# P-MT3620RDB-1-7_PMU.net
KiCad netlist of a schematic drawn in Altium Designer
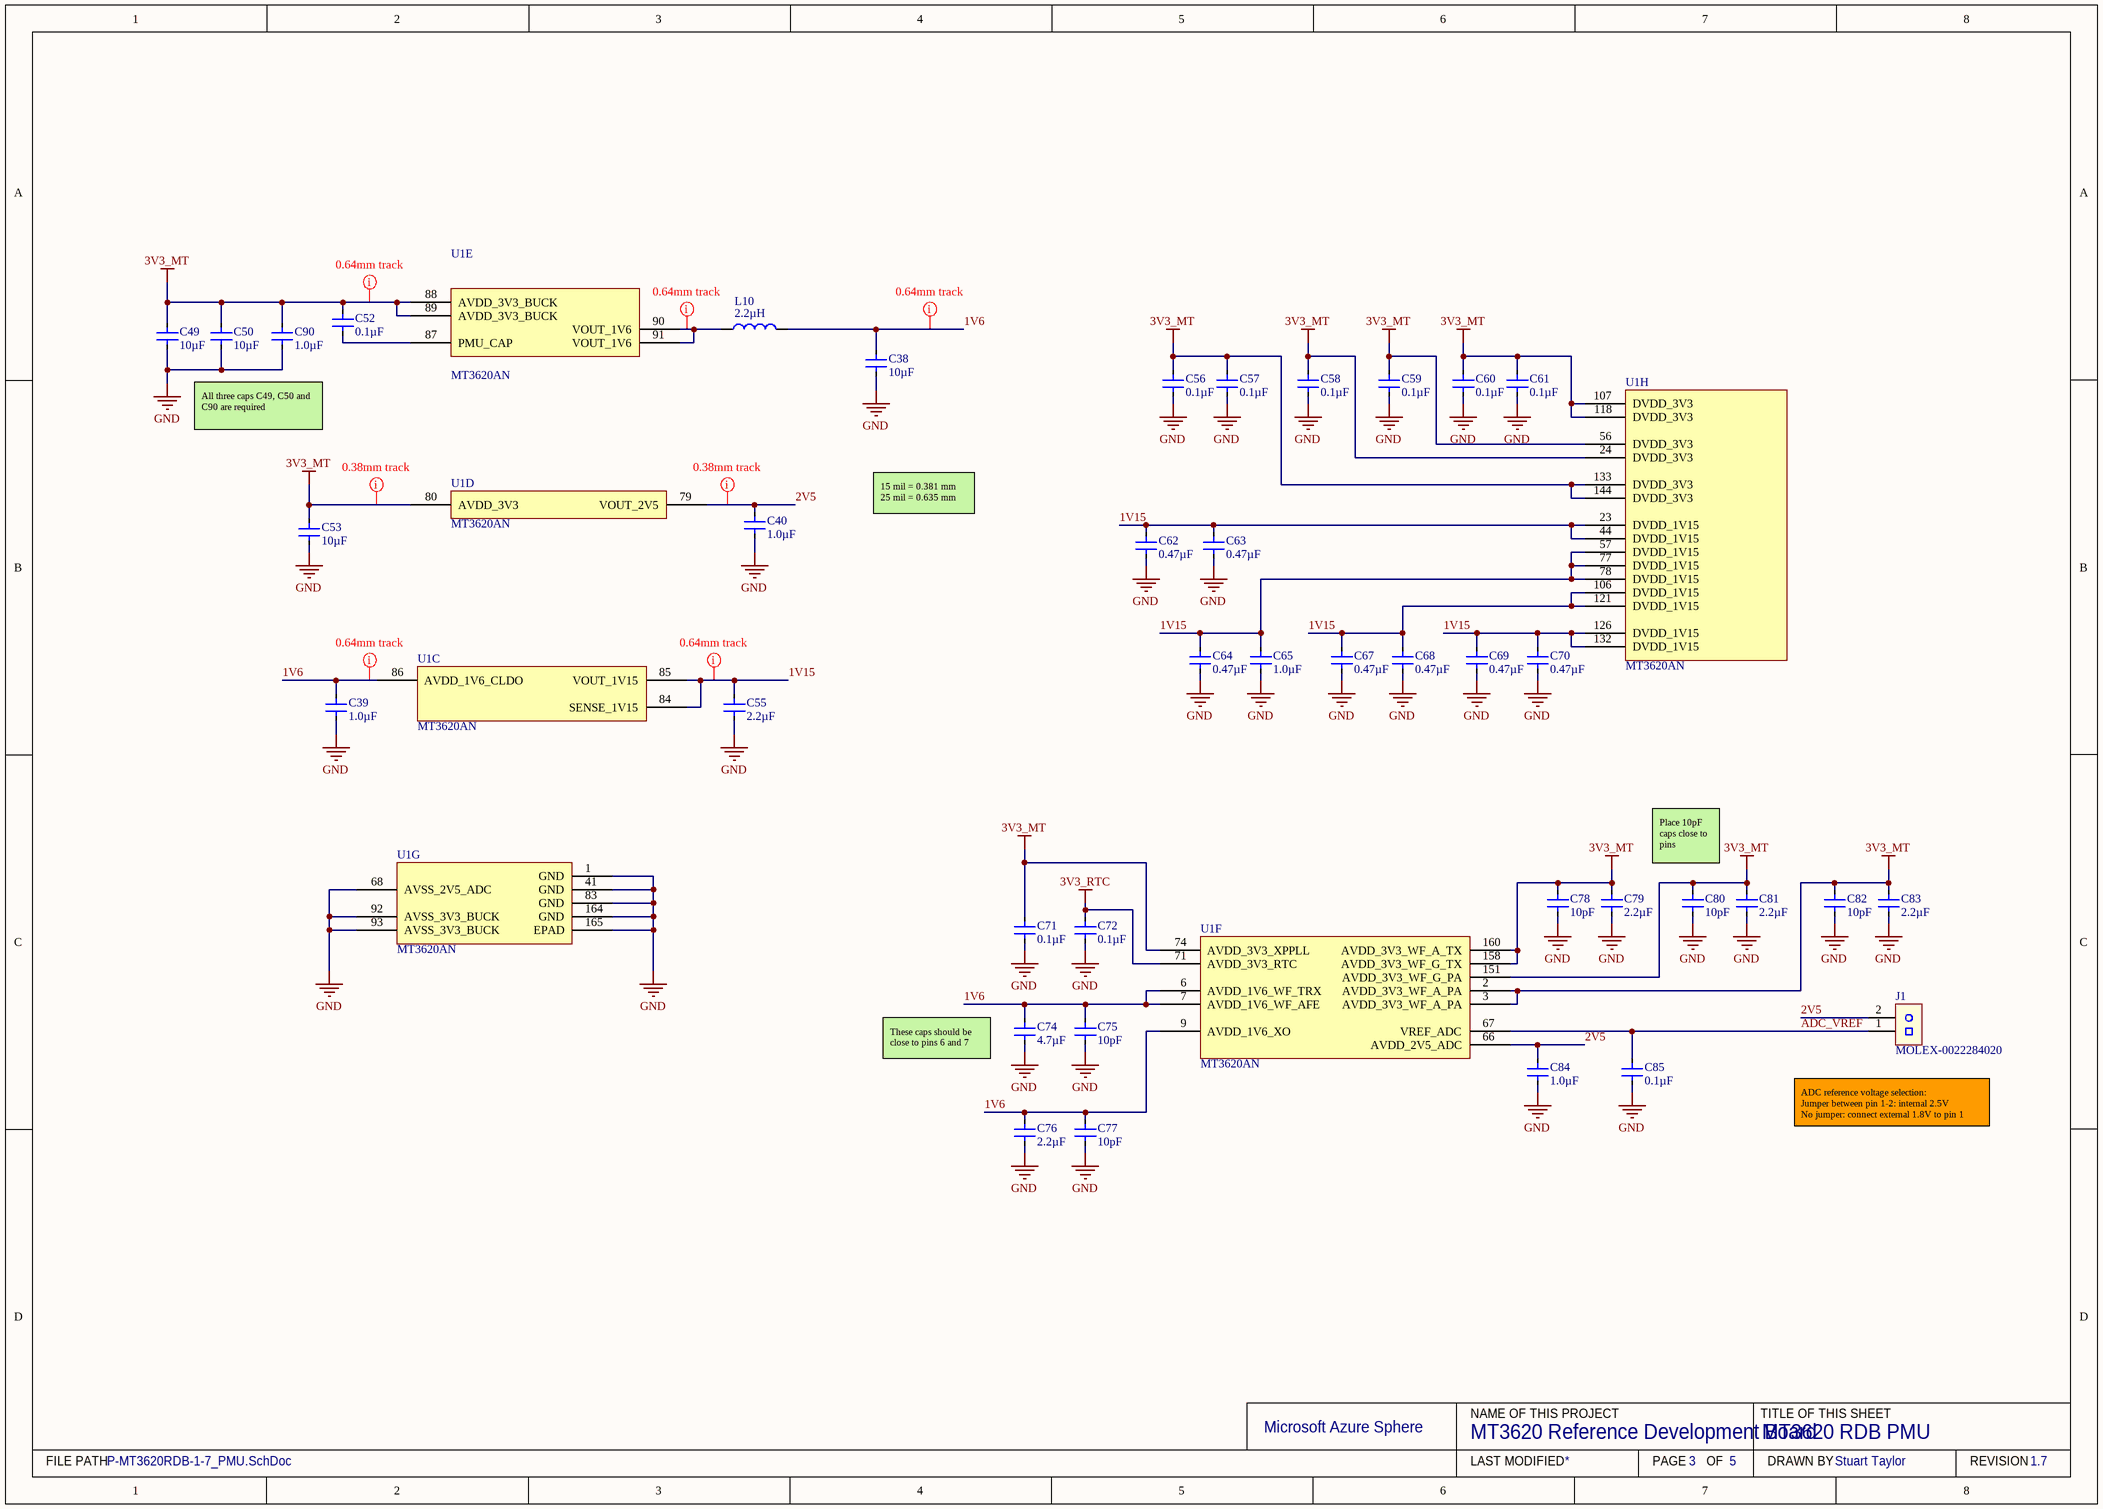
[diagram p0: P-MT3620RDB-1-7_PMU.SchDoc]

(export (version "E")
  (design (tool "Eeschema 10.0.6"))
  (components
    (comp (ref "C38")
      (value "10µF")
      (footprint "CAPC1608-EIA0603-1MM-MED")
      (description "CAP CER 10UF 25V 20% X5R 0603")
      (fields
        (field (name "MANUFACTURER") "TDK Corporation")
        (field (name "MANUFACTURER PART NUMBER") "C1608X5R1E106M080AC")
        (field (name "CAPACITANCE") "10µF")
      )
      (libsource (lib "TDK-Capacitor_C_0603") (part "10µF 0603 X5R 25V"))
    )
    (comp (ref "C39")
      (value "1.0µF")
      (footprint "CAPC1005-EIA0402 0.55MM MED")
      (description "CAP CER 1UF 35V 10% X5R 0402")
      (fields
        (field (name "MANUFACTURER") "TDK Corporation")
        (field (name "MANUFACTURER PART NUMBER") "C1005X5R1V105K050BC")
        (field (name "CAPACITANCE") "1.0µF")
      )
      (libsource (lib "TDK_Capacitor_C_0402") (part "1.0µF 0402 X5R 35V"))
    )
    (comp (ref "C40")
      (value "1.0µF")
      (footprint "CAPC1005-EIA0402 0.55MM MED")
      (description "CAP CER 1UF 35V 10% X5R 0402")
      (fields
        (field (name "MANUFACTURER") "TDK Corporation")
        (field (name "MANUFACTURER PART NUMBER") "C1005X5R1V105K050BC")
        (field (name "CAPACITANCE") "1.0µF")
      )
      (libsource (lib "TDK_Capacitor_C_0402") (part "1.0µF 0402 X5R 35V"))
    )
    (comp (ref "C49")
      (value "10µF")
      (footprint "CAPC1005-EIA0402 0.55MM MED")
      (description "CAP CER 10UF 6.3V 20% X5R 0402")
      (fields
        (field (name "MANUFACTURER") "TDK Corporation")
        (field (name "MANUFACTURER PART NUMBER") "C1005X5R0J106M050BC")
        (field (name "CAPACITANCE") "10µF")
      )
      (libsource (lib "TDK_Capacitor_C_0402") (part "10µF 0402 X5R 6.3V"))
    )
    (comp (ref "C50")
      (value "10µF")
      (footprint "CAPC1005-EIA0402 0.55MM MED")
      (description "CAP CER 10UF 6.3V 20% X5R 0402")
      (fields
        (field (name "MANUFACTURER") "TDK Corporation")
        (field (name "MANUFACTURER PART NUMBER") "C1005X5R0J106M050BC")
        (field (name "CAPACITANCE") "10µF")
      )
      (libsource (lib "TDK_Capacitor_C_0402") (part "10µF 0402 X5R 6.3V"))
    )
    (comp (ref "C52")
      (value "0.1µF")
      (footprint "CAPC1005-EIA0402 0.55MM MED")
      (description "CAP CER 0.1UF 50V 10% X7R 0402")
      (fields
        (field (name "MANUFACTURER") "TDK Corporation")
        (field (name "MANUFACTURER PART NUMBER") "C1005X7R1H104K050BB")
        (field (name "CAPACITANCE") "0.1µF")
      )
      (libsource (lib "TDK_Capacitor_C_0402") (part "0.1µF 0402 X7R 50V"))
    )
    (comp (ref "C53")
      (value "10µF")
      (footprint "CAPC1005-EIA0402 0.55MM MED")
      (description "CAP CER 10UF 6.3V 20% X5R 0402")
      (fields
        (field (name "MANUFACTURER") "TDK Corporation")
        (field (name "MANUFACTURER PART NUMBER") "C1005X5R0J106M050BC")
        (field (name "CAPACITANCE") "10µF")
      )
      (libsource (lib "TDK_Capacitor_C_0402") (part "10µF 0402 X5R 6.3V"))
    )
    (comp (ref "C55")
      (value "2.2µF")
      (footprint "CAPC1005-EIA0402 0.55MM MED")
      (description "CAP CER 2.2UF 35V 10% X5R 0402")
      (fields
        (field (name "MANUFACTURER") "TDK Corporation")
        (field (name "MANUFACTURER PART NUMBER") "C1005X5R1V225K050BC")
        (field (name "CAPACITANCE") "2.2µF")
      )
      (libsource (lib "TDK_Capacitor_C_0402") (part "2.2µF 0402 X5R 35V"))
    )
    (comp (ref "C56")
      (value "0.1µF")
      (footprint "CAPC1005-EIA0402 0.55MM MED")
      (description "CAP CER 0.1UF 50V 10% X7R 0402")
      (fields
        (field (name "MANUFACTURER") "TDK Corporation")
        (field (name "MANUFACTURER PART NUMBER") "C1005X7R1H104K050BB")
        (field (name "CAPACITANCE") "0.1µF")
      )
      (libsource (lib "TDK_Capacitor_C_0402") (part "0.1µF 0402 X7R 50V"))
    )
    (comp (ref "C57")
      (value "0.1µF")
      (footprint "CAPC1005-EIA0402 0.55MM MED")
      (description "CAP CER 0.1UF 50V 10% X7R 0402")
      (fields
        (field (name "MANUFACTURER") "TDK Corporation")
        (field (name "MANUFACTURER PART NUMBER") "C1005X7R1H104K050BB")
        (field (name "CAPACITANCE") "0.1µF")
      )
      (libsource (lib "TDK_Capacitor_C_0402") (part "0.1µF 0402 X7R 50V"))
    )
    (comp (ref "C58")
      (value "0.1µF")
      (footprint "CAPC1005-EIA0402 0.55MM MED")
      (description "CAP CER 0.1UF 50V 10% X7R 0402")
      (fields
        (field (name "MANUFACTURER") "TDK Corporation")
        (field (name "MANUFACTURER PART NUMBER") "C1005X7R1H104K050BB")
        (field (name "CAPACITANCE") "0.1µF")
      )
      (libsource (lib "TDK_Capacitor_C_0402") (part "0.1µF 0402 X7R 50V"))
    )
    (comp (ref "C59")
      (value "0.1µF")
      (footprint "CAPC1005-EIA0402 0.55MM MED")
      (description "CAP CER 0.1UF 50V 10% X7R 0402")
      (fields
        (field (name "MANUFACTURER") "TDK Corporation")
        (field (name "MANUFACTURER PART NUMBER") "C1005X7R1H104K050BB")
        (field (name "CAPACITANCE") "0.1µF")
      )
      (libsource (lib "TDK_Capacitor_C_0402") (part "0.1µF 0402 X7R 50V"))
    )
    (comp (ref "C60")
      (value "0.1µF")
      (footprint "CAPC1005-EIA0402 0.55MM MED")
      (description "CAP CER 0.1UF 50V 10% X7R 0402")
      (fields
        (field (name "MANUFACTURER") "TDK Corporation")
        (field (name "MANUFACTURER PART NUMBER") "C1005X7R1H104K050BB")
        (field (name "CAPACITANCE") "0.1µF")
      )
      (libsource (lib "TDK_Capacitor_C_0402") (part "0.1µF 0402 X7R 50V"))
    )
    (comp (ref "C61")
      (value "0.1µF")
      (footprint "CAPC1005-EIA0402 0.55MM MED")
      (description "CAP CER 0.1UF 50V 10% X7R 0402")
      (fields
        (field (name "MANUFACTURER") "TDK Corporation")
        (field (name "MANUFACTURER PART NUMBER") "C1005X7R1H104K050BB")
        (field (name "CAPACITANCE") "0.1µF")
      )
      (libsource (lib "TDK_Capacitor_C_0402") (part "0.1µF 0402 X7R 50V"))
    )
    (comp (ref "C62")
      (value "0.47µF")
      (footprint "CAPC1005-EIA0402 0.55MM MED")
      (description "CAP CER 0.47UF 35V 10% X5R 0402")
      (fields
        (field (name "MANUFACTURER") "TDK Corporation")
        (field (name "MANUFACTURER PART NUMBER") "C1005X5R1V474K050BC")
        (field (name "CAPACITANCE") "0.47µF")
      )
      (libsource (lib "TDK_Capacitor_C_0402") (part "0.47µF 0402 X5R 35V"))
    )
    (comp (ref "C63")
      (value "0.47µF")
      (footprint "CAPC1005-EIA0402 0.55MM MED")
      (description "CAP CER 0.47UF 35V 10% X5R 0402")
      (fields
        (field (name "MANUFACTURER") "TDK Corporation")
        (field (name "MANUFACTURER PART NUMBER") "C1005X5R1V474K050BC")
        (field (name "CAPACITANCE") "0.47µF")
      )
      (libsource (lib "TDK_Capacitor_C_0402") (part "0.47µF 0402 X5R 35V"))
    )
    (comp (ref "C64")
      (value "0.47µF")
      (footprint "CAPC1005-EIA0402 0.55MM MED")
      (description "CAP CER 0.47UF 35V 10% X5R 0402")
      (fields
        (field (name "MANUFACTURER") "TDK Corporation")
        (field (name "MANUFACTURER PART NUMBER") "C1005X5R1V474K050BC")
        (field (name "CAPACITANCE") "0.47µF")
      )
      (libsource (lib "TDK_Capacitor_C_0402") (part "0.47µF 0402 X5R 35V"))
    )
    (comp (ref "C65")
      (value "1.0µF")
      (footprint "CAPC1005-EIA0402 0.55MM MED")
      (description "CAP CER 1UF 35V 10% X5R 0402")
      (fields
        (field (name "MANUFACTURER") "TDK Corporation")
        (field (name "MANUFACTURER PART NUMBER") "C1005X5R1V105K050BC")
        (field (name "CAPACITANCE") "1.0µF")
      )
      (libsource (lib "TDK_Capacitor_C_0402") (part "1.0µF 0402 X5R 35V"))
    )
    (comp (ref "C67")
      (value "0.47µF")
      (footprint "CAPC1005-EIA0402 0.55MM MED")
      (description "CAP CER 0.47UF 35V 10% X5R 0402")
      (fields
        (field (name "MANUFACTURER") "TDK Corporation")
        (field (name "MANUFACTURER PART NUMBER") "C1005X5R1V474K050BC")
        (field (name "CAPACITANCE") "0.47µF")
      )
      (libsource (lib "TDK_Capacitor_C_0402") (part "0.47µF 0402 X5R 35V"))
    )
    (comp (ref "C68")
      (value "0.47µF")
      (footprint "CAPC1005-EIA0402 0.55MM MED")
      (description "CAP CER 0.47UF 35V 10% X5R 0402")
      (fields
        (field (name "MANUFACTURER") "TDK Corporation")
        (field (name "MANUFACTURER PART NUMBER") "C1005X5R1V474K050BC")
        (field (name "CAPACITANCE") "0.47µF")
      )
      (libsource (lib "TDK_Capacitor_C_0402") (part "0.47µF 0402 X5R 35V"))
    )
    (comp (ref "C69")
      (value "0.47µF")
      (footprint "CAPC1005-EIA0402 0.55MM MED")
      (description "CAP CER 0.47UF 35V 10% X5R 0402")
      (fields
        (field (name "MANUFACTURER") "TDK Corporation")
        (field (name "MANUFACTURER PART NUMBER") "C1005X5R1V474K050BC")
        (field (name "CAPACITANCE") "0.47µF")
      )
      (libsource (lib "TDK_Capacitor_C_0402") (part "0.47µF 0402 X5R 35V"))
    )
    (comp (ref "C70")
      (value "0.47µF")
      (footprint "CAPC1005-EIA0402 0.55MM MED")
      (description "CAP CER 0.47UF 35V 10% X5R 0402")
      (fields
        (field (name "MANUFACTURER") "TDK Corporation")
        (field (name "MANUFACTURER PART NUMBER") "C1005X5R1V474K050BC")
        (field (name "CAPACITANCE") "0.47µF")
      )
      (libsource (lib "TDK_Capacitor_C_0402") (part "0.47µF 0402 X5R 35V"))
    )
    (comp (ref "C71")
      (value "0.1µF")
      (footprint "CAPC1005-EIA0402 0.55MM MED")
      (description "CAP CER 0.1UF 50V 10% X7R 0402")
      (fields
        (field (name "MANUFACTURER") "TDK Corporation")
        (field (name "MANUFACTURER PART NUMBER") "C1005X7R1H104K050BB")
        (field (name "CAPACITANCE") "0.1µF")
      )
      (libsource (lib "TDK_Capacitor_C_0402") (part "0.1µF 0402 X7R 50V"))
    )
    (comp (ref "C72")
      (value "0.1µF")
      (footprint "CAPC1005-EIA0402 0.55MM MED")
      (description "CAP CER 0.1UF 50V 10% X7R 0402")
      (fields
        (field (name "MANUFACTURER") "TDK Corporation")
        (field (name "MANUFACTURER PART NUMBER") "C1005X7R1H104K050BB")
        (field (name "CAPACITANCE") "0.1µF")
      )
      (libsource (lib "TDK_Capacitor_C_0402") (part "0.1µF 0402 X7R 50V"))
    )
    (comp (ref "C74")
      (value "4.7µF")
      (footprint "CAPC1005-EIA0402 0.55MM MED")
      (description "CAP CER 4.7UF 10V 10% X5R 0402")
      (fields
        (field (name "MANUFACTURER") "TDK Corporation")
        (field (name "MANUFACTURER PART NUMBER") "C1005X5R1A475K050BC")
        (field (name "CAPACITANCE") "4.7µF")
      )
      (libsource (lib "TDK_Capacitor_C_0402") (part "4.7µF 0402 X5R 10V"))
    )
    (comp (ref "C75")
      (value "10pF")
      (footprint "CAPC1005-EIA0402 0.55MM MED")
      (description "CAP CER 10PF 50V NP0 0402")
      (fields
        (field (name "MANUFACTURER") "TDK Corporation")
        (field (name "MANUFACTURER PART NUMBER") "C1005C0G1H100D050BA")
        (field (name "CAPACITANCE") "10pF")
      )
      (libsource (lib "TDK_Capacitor_C_0402") (part "10pF 0402 C0G, NP0 50V"))
    )
    (comp (ref "C76")
      (value "2.2µF")
      (footprint "CAPC1005-EIA0402 0.55MM MED")
      (description "CAP CER 2.2UF 35V 10% X5R 0402")
      (fields
        (field (name "MANUFACTURER") "TDK Corporation")
        (field (name "MANUFACTURER PART NUMBER") "C1005X5R1V225K050BC")
        (field (name "CAPACITANCE") "2.2µF")
      )
      (libsource (lib "TDK_Capacitor_C_0402") (part "2.2µF 0402 X5R 35V"))
    )
    (comp (ref "C77")
      (value "10pF")
      (footprint "CAPC1005-EIA0402 0.55MM MED")
      (description "CAP CER 10PF 50V NP0 0402")
      (fields
        (field (name "MANUFACTURER") "TDK Corporation")
        (field (name "MANUFACTURER PART NUMBER") "C1005C0G1H100D050BA")
        (field (name "CAPACITANCE") "10pF")
      )
      (libsource (lib "TDK_Capacitor_C_0402") (part "10pF 0402 C0G, NP0 50V"))
    )
    (comp (ref "C78")
      (value "10pF")
      (footprint "CAPC1005-EIA0402 0.55MM MED")
      (description "CAP CER 10PF 50V NP0 0402")
      (fields
        (field (name "MANUFACTURER") "TDK Corporation")
        (field (name "MANUFACTURER PART NUMBER") "C1005C0G1H100D050BA")
        (field (name "CAPACITANCE") "10pF")
      )
      (libsource (lib "TDK_Capacitor_C_0402") (part "10pF 0402 C0G, NP0 50V"))
    )
    (comp (ref "C79")
      (value "2.2µF")
      (footprint "CAPC1005-EIA0402 0.55MM MED")
      (description "CAP CER 2.2UF 35V 10% X5R 0402")
      (fields
        (field (name "MANUFACTURER") "TDK Corporation")
        (field (name "MANUFACTURER PART NUMBER") "C1005X5R1V225K050BC")
        (field (name "CAPACITANCE") "2.2µF")
      )
      (libsource (lib "TDK_Capacitor_C_0402") (part "2.2µF 0402 X5R 35V"))
    )
    (comp (ref "C80")
      (value "10pF")
      (footprint "CAPC1005-EIA0402 0.55MM MED")
      (description "CAP CER 10PF 50V NP0 0402")
      (fields
        (field (name "MANUFACTURER") "TDK Corporation")
        (field (name "MANUFACTURER PART NUMBER") "C1005C0G1H100D050BA")
        (field (name "CAPACITANCE") "10pF")
      )
      (libsource (lib "TDK_Capacitor_C_0402") (part "10pF 0402 C0G, NP0 50V"))
    )
    (comp (ref "C81")
      (value "2.2µF")
      (footprint "CAPC1005-EIA0402 0.55MM MED")
      (description "CAP CER 2.2UF 35V 10% X5R 0402")
      (fields
        (field (name "MANUFACTURER") "TDK Corporation")
        (field (name "MANUFACTURER PART NUMBER") "C1005X5R1V225K050BC")
        (field (name "CAPACITANCE") "2.2µF")
      )
      (libsource (lib "TDK_Capacitor_C_0402") (part "2.2µF 0402 X5R 35V"))
    )
    (comp (ref "C82")
      (value "10pF")
      (footprint "CAPC1005-EIA0402 0.55MM MED")
      (description "CAP CER 10PF 50V NP0 0402")
      (fields
        (field (name "MANUFACTURER") "TDK Corporation")
        (field (name "MANUFACTURER PART NUMBER") "C1005C0G1H100D050BA")
        (field (name "CAPACITANCE") "10pF")
      )
      (libsource (lib "TDK_Capacitor_C_0402") (part "10pF 0402 C0G, NP0 50V"))
    )
    (comp (ref "C83")
      (value "2.2µF")
      (footprint "CAPC1005-EIA0402 0.55MM MED")
      (description "CAP CER 2.2UF 35V 10% X5R 0402")
      (fields
        (field (name "MANUFACTURER") "TDK Corporation")
        (field (name "MANUFACTURER PART NUMBER") "C1005X5R1V225K050BC")
        (field (name "CAPACITANCE") "2.2µF")
      )
      (libsource (lib "TDK_Capacitor_C_0402") (part "2.2µF 0402 X5R 35V"))
    )
    (comp (ref "C84")
      (value "1.0µF")
      (footprint "CAPC1005-EIA0402 0.55MM MED")
      (description "CAP CER 1UF 35V 10% X5R 0402")
      (fields
        (field (name "MANUFACTURER") "TDK Corporation")
        (field (name "MANUFACTURER PART NUMBER") "C1005X5R1V105K050BC")
        (field (name "CAPACITANCE") "1.0µF")
      )
      (libsource (lib "TDK_Capacitor_C_0402") (part "1.0µF 0402 X5R 35V"))
    )
    (comp (ref "C85")
      (value "0.1µF")
      (footprint "CAPC1005-EIA0402 0.55MM MED")
      (description "CAP CER 0.1UF 50V 10% X7R 0402")
      (fields
        (field (name "MANUFACTURER") "TDK Corporation")
        (field (name "MANUFACTURER PART NUMBER") "C1005X7R1H104K050BB")
        (field (name "CAPACITANCE") "0.1µF")
      )
      (libsource (lib "TDK_Capacitor_C_0402") (part "0.1µF 0402 X7R 50V"))
    )
    (comp (ref "C90")
      (value "1.0µF")
      (footprint "CAPC1005-EIA0402 0.55MM MED")
      (description "CAP CER 1UF 35V 10% X5R 0402")
      (fields
        (field (name "MANUFACTURER") "TDK Corporation")
        (field (name "MANUFACTURER PART NUMBER") "C1005X5R1V105K050BC")
        (field (name "CAPACITANCE") "1.0µF")
      )
      (libsource (lib "TDK_Capacitor_C_0402") (part "1.0µF 0402 X5R 35V"))
    )
    (comp (ref "J1")
      (value "MOLEX-0022284020")
      (footprint "0022284020")
      (description "CONN HEADER 2POS .100 VERT TIN")
      (fields
        (field (name "MANUFACTURER") "Molex, LLC")
        (field (name "MANUFACTURER PART NUMBER") "0022284020")
      )
      (libsource (lib "Molex") (part "MOLEX-0022284020"))
    )
    (comp (ref "L10")
      (value "2.2µH")
      (footprint "MAMK2520T2R2M")
      (description "FIXED IND 2.2UH 1.9A 117 MOHM")
      (fields
        (field (name "MANUFACTURER") "Taiyo Yuden")
        (field (name "MANUFACTURER PART NUMBER") "MAMK2520T2R2M")
      )
      (libsource (lib "TaiyoYuden ") (part "MAMK2520T2R2M"))
    )
    (comp (ref "U1")
      (value "MT3620AN")
      (footprint "MT3620_MaskSquaresVias50")
      (fields (field (name "MANUFACTURER") "MediaTek Inc."))
      (libsource (lib "Microsoft") (part "MT3620AN"))
    )
  )
  (nets
    (net (code "1") (name "/1V6") (class "Default")
      (node (ref "C38") (pin "2") (pinfunction "2_2") (pintype "passive"))
      (node (ref "C39") (pin "2") (pinfunction "2_2") (pintype "passive"))
      (node (ref "C74") (pin "2") (pinfunction "2_2") (pintype "passive"))
      (node (ref "C75") (pin "2") (pinfunction "2_2") (pintype "passive"))
      (node (ref "C76") (pin "2") (pinfunction "2_2") (pintype "passive"))
      (node (ref "C77") (pin "2") (pinfunction "2_2") (pintype "passive"))
      (node (ref "L10") (pin "2") (pinfunction "2_2") (pintype "passive"))
      (node (ref "U1") (pin "6") (pinfunction "AVDD_1V6_WF_TRX_6") (pintype "passive"))
      (node (ref "U1") (pin "7") (pinfunction "AVDD_1V6_WF_AFE_7") (pintype "passive"))
      (node (ref "U1") (pin "86") (pinfunction "AVDD_1V6_CLDO_86") (pintype "passive"))
      (node (ref "U1") (pin "9") (pinfunction "AVDD_1V6_XO_9") (pintype "passive"))
    )
    (net (code "2") (name "/1V15") (class "Default")
      (node (ref "C55") (pin "2") (pinfunction "2_2") (pintype "passive"))
      (node (ref "C62") (pin "2") (pinfunction "2_2") (pintype "passive"))
      (node (ref "C63") (pin "2") (pinfunction "2_2") (pintype "passive"))
      (node (ref "C64") (pin "2") (pinfunction "2_2") (pintype "passive"))
      (node (ref "C65") (pin "2") (pinfunction "2_2") (pintype "passive"))
      (node (ref "C67") (pin "2") (pinfunction "2_2") (pintype "passive"))
      (node (ref "C68") (pin "2") (pinfunction "2_2") (pintype "passive"))
      (node (ref "C69") (pin "2") (pinfunction "2_2") (pintype "passive"))
      (node (ref "C70") (pin "2") (pinfunction "2_2") (pintype "passive"))
      (node (ref "U1") (pin "106") (pinfunction "DVDD_1V15_106") (pintype "passive"))
      (node (ref "U1") (pin "121") (pinfunction "DVDD_1V15_121") (pintype "passive"))
      (node (ref "U1") (pin "126") (pinfunction "DVDD_1V15_126") (pintype "passive"))
      (node (ref "U1") (pin "132") (pinfunction "DVDD_1V15_132") (pintype "passive"))
      (node (ref "U1") (pin "23") (pinfunction "DVDD_1V15_23") (pintype "passive"))
      (node (ref "U1") (pin "44") (pinfunction "DVDD_1V15_44") (pintype "passive"))
      (node (ref "U1") (pin "57") (pinfunction "DVDD_1V15_57") (pintype "passive"))
      (node (ref "U1") (pin "77") (pinfunction "DVDD_1V15_77") (pintype "passive"))
      (node (ref "U1") (pin "78") (pinfunction "DVDD_1V15_78") (pintype "passive"))
      (node (ref "U1") (pin "84") (pinfunction "SENSE_1V15_84") (pintype "passive"))
      (node (ref "U1") (pin "85") (pinfunction "VOUT_1V15_85") (pintype "passive"))
    )
    (net (code "3") (name "/2V5") (class "Default")
      (node (ref "C40") (pin "2") (pinfunction "2_2") (pintype "passive"))
      (node (ref "C84") (pin "2") (pinfunction "2_2") (pintype "passive"))
      (node (ref "J1") (pin "2") (pinfunction "2_2") (pintype "passive"))
      (node (ref "U1") (pin "66") (pinfunction "AVDD_2V5_ADC_66") (pintype "passive"))
      (node (ref "U1") (pin "79") (pinfunction "VOUT_2V5_79") (pintype "passive"))
    )
    (net (code "4") (name "/ADC_VREF") (class "Default")
      (node (ref "C85") (pin "2") (pinfunction "2_2") (pintype "passive"))
      (node (ref "J1") (pin "1") (pinfunction "1_1") (pintype "passive"))
      (node (ref "U1") (pin "67") (pinfunction "VREF_ADC_67") (pintype "passive"))
    )
    (net (code "5") (name "3V3_MT") (class "Default")
      (node (ref "C49") (pin "2") (pinfunction "2_2") (pintype "passive"))
      (node (ref "C50") (pin "2") (pinfunction "2_2") (pintype "passive"))
      (node (ref "C52") (pin "2") (pinfunction "2_2") (pintype "passive"))
      (node (ref "C53") (pin "2") (pinfunction "2_2") (pintype "passive"))
      (node (ref "C56") (pin "2") (pinfunction "2_2") (pintype "passive"))
      (node (ref "C57") (pin "2") (pinfunction "2_2") (pintype "passive"))
      (node (ref "C58") (pin "2") (pinfunction "2_2") (pintype "passive"))
      (node (ref "C59") (pin "2") (pinfunction "2_2") (pintype "passive"))
      (node (ref "C60") (pin "2") (pinfunction "2_2") (pintype "passive"))
      (node (ref "C61") (pin "2") (pinfunction "2_2") (pintype "passive"))
      (node (ref "C71") (pin "2") (pinfunction "2_2") (pintype "passive"))
      (node (ref "C78") (pin "2") (pinfunction "2_2") (pintype "passive"))
      (node (ref "C79") (pin "2") (pinfunction "2_2") (pintype "passive"))
      (node (ref "C80") (pin "2") (pinfunction "2_2") (pintype "passive"))
      (node (ref "C81") (pin "2") (pinfunction "2_2") (pintype "passive"))
      (node (ref "C82") (pin "2") (pinfunction "2_2") (pintype "passive"))
      (node (ref "C83") (pin "2") (pinfunction "2_2") (pintype "passive"))
      (node (ref "C90") (pin "2") (pinfunction "2_2") (pintype "passive"))
      (node (ref "U1") (pin "107") (pinfunction "DVDD_3V3_107") (pintype "passive"))
      (node (ref "U1") (pin "118") (pinfunction "DVDD_3V3_118") (pintype "passive"))
      (node (ref "U1") (pin "133") (pinfunction "DVDD_3V3_133") (pintype "passive"))
      (node (ref "U1") (pin "144") (pinfunction "DVDD_3V3_144") (pintype "passive"))
      (node (ref "U1") (pin "151") (pinfunction "AVDD_3V3_WF_G_PA_151") (pintype "passive"))
      (node (ref "U1") (pin "158") (pinfunction "AVDD_3V3_WF_G_TX_158") (pintype "passive"))
      (node (ref "U1") (pin "160") (pinfunction "AVDD_3V3_WF_A_TX_160") (pintype "passive"))
      (node (ref "U1") (pin "2") (pinfunction "AVDD_3V3_WF_A_PA_2") (pintype "passive"))
      (node (ref "U1") (pin "24") (pinfunction "DVDD_3V3_24") (pintype "passive"))
      (node (ref "U1") (pin "3") (pinfunction "AVDD_3V3_WF_A_PA_3") (pintype "passive"))
      (node (ref "U1") (pin "56") (pinfunction "DVDD_3V3_56") (pintype "passive"))
      (node (ref "U1") (pin "74") (pinfunction "AVDD_3V3_XPPLL_74") (pintype "passive"))
      (node (ref "U1") (pin "80") (pinfunction "AVDD_3V3_80") (pintype "passive"))
      (node (ref "U1") (pin "88") (pinfunction "AVDD_3V3_BUCK_88") (pintype "passive"))
      (node (ref "U1") (pin "89") (pinfunction "AVDD_3V3_BUCK_89") (pintype "passive"))
    )
    (net (code "6") (name "3V3_RTC") (class "Default")
      (node (ref "C72") (pin "2") (pinfunction "2_2") (pintype "passive"))
      (node (ref "U1") (pin "71") (pinfunction "AVDD_3V3_RTC_71") (pintype "passive"))
    )
    (net (code "7") (name "GND") (class "Default")
      (node (ref "C38") (pin "1") (pinfunction "1_1") (pintype "passive"))
      (node (ref "C39") (pin "1") (pinfunction "1_1") (pintype "passive"))
      (node (ref "C40") (pin "1") (pinfunction "1_1") (pintype "passive"))
      (node (ref "C49") (pin "1") (pinfunction "1_1") (pintype "passive"))
      (node (ref "C50") (pin "1") (pinfunction "1_1") (pintype "passive"))
      (node (ref "C53") (pin "1") (pinfunction "1_1") (pintype "passive"))
      (node (ref "C55") (pin "1") (pinfunction "1_1") (pintype "passive"))
      (node (ref "C56") (pin "1") (pinfunction "1_1") (pintype "passive"))
      (node (ref "C57") (pin "1") (pinfunction "1_1") (pintype "passive"))
      (node (ref "C58") (pin "1") (pinfunction "1_1") (pintype "passive"))
      (node (ref "C59") (pin "1") (pinfunction "1_1") (pintype "passive"))
      (node (ref "C60") (pin "1") (pinfunction "1_1") (pintype "passive"))
      (node (ref "C61") (pin "1") (pinfunction "1_1") (pintype "passive"))
      (node (ref "C62") (pin "1") (pinfunction "1_1") (pintype "passive"))
      (node (ref "C63") (pin "1") (pinfunction "1_1") (pintype "passive"))
      (node (ref "C64") (pin "1") (pinfunction "1_1") (pintype "passive"))
      (node (ref "C65") (pin "1") (pinfunction "1_1") (pintype "passive"))
      (node (ref "C67") (pin "1") (pinfunction "1_1") (pintype "passive"))
      (node (ref "C68") (pin "1") (pinfunction "1_1") (pintype "passive"))
      (node (ref "C69") (pin "1") (pinfunction "1_1") (pintype "passive"))
      (node (ref "C70") (pin "1") (pinfunction "1_1") (pintype "passive"))
      (node (ref "C71") (pin "1") (pinfunction "1_1") (pintype "passive"))
      (node (ref "C72") (pin "1") (pinfunction "1_1") (pintype "passive"))
      (node (ref "C74") (pin "1") (pinfunction "1_1") (pintype "passive"))
      (node (ref "C75") (pin "1") (pinfunction "1_1") (pintype "passive"))
      (node (ref "C76") (pin "1") (pinfunction "1_1") (pintype "passive"))
      (node (ref "C77") (pin "1") (pinfunction "1_1") (pintype "passive"))
      (node (ref "C78") (pin "1") (pinfunction "1_1") (pintype "passive"))
      (node (ref "C79") (pin "1") (pinfunction "1_1") (pintype "passive"))
      (node (ref "C80") (pin "1") (pinfunction "1_1") (pintype "passive"))
      (node (ref "C81") (pin "1") (pinfunction "1_1") (pintype "passive"))
      (node (ref "C82") (pin "1") (pinfunction "1_1") (pintype "passive"))
      (node (ref "C83") (pin "1") (pinfunction "1_1") (pintype "passive"))
      (node (ref "C84") (pin "1") (pinfunction "1_1") (pintype "passive"))
      (node (ref "C85") (pin "1") (pinfunction "1_1") (pintype "passive"))
      (node (ref "C90") (pin "1") (pinfunction "1_1") (pintype "passive"))
      (node (ref "U1") (pin "1") (pinfunction "GND_1") (pintype "passive"))
      (node (ref "U1") (pin "164") (pinfunction "GND_164") (pintype "passive"))
      (node (ref "U1") (pin "165") (pinfunction "EPAD_165") (pintype "passive"))
      (node (ref "U1") (pin "41") (pinfunction "GND_41") (pintype "passive"))
      (node (ref "U1") (pin "68") (pinfunction "AVSS_2V5_ADC_68") (pintype "passive"))
      (node (ref "U1") (pin "83") (pinfunction "GND_83") (pintype "passive"))
      (node (ref "U1") (pin "92") (pinfunction "AVSS_3V3_BUCK_92") (pintype "passive"))
      (node (ref "U1") (pin "93") (pinfunction "AVSS_3V3_BUCK_93") (pintype "passive"))
    )
    (net (code "8") (name "Net-(L10-Pad1)") (class "Default")
      (node (ref "L10") (pin "1") (pinfunction "1_1") (pintype "passive"))
      (node (ref "U1") (pin "90") (pinfunction "VOUT_1V6_90") (pintype "passive"))
      (node (ref "U1") (pin "91") (pinfunction "VOUT_1V6_91") (pintype "passive"))
    )
    (net (code "9") (name "Net-(U1E-PMU_CAP)") (class "Default")
      (node (ref "C52") (pin "1") (pinfunction "1_1") (pintype "passive"))
      (node (ref "U1") (pin "87") (pinfunction "PMU_CAP_87") (pintype "passive"))
    )
  )
)
